# osccc.net
KiCad netlist of a schematic drawn in EAGLE
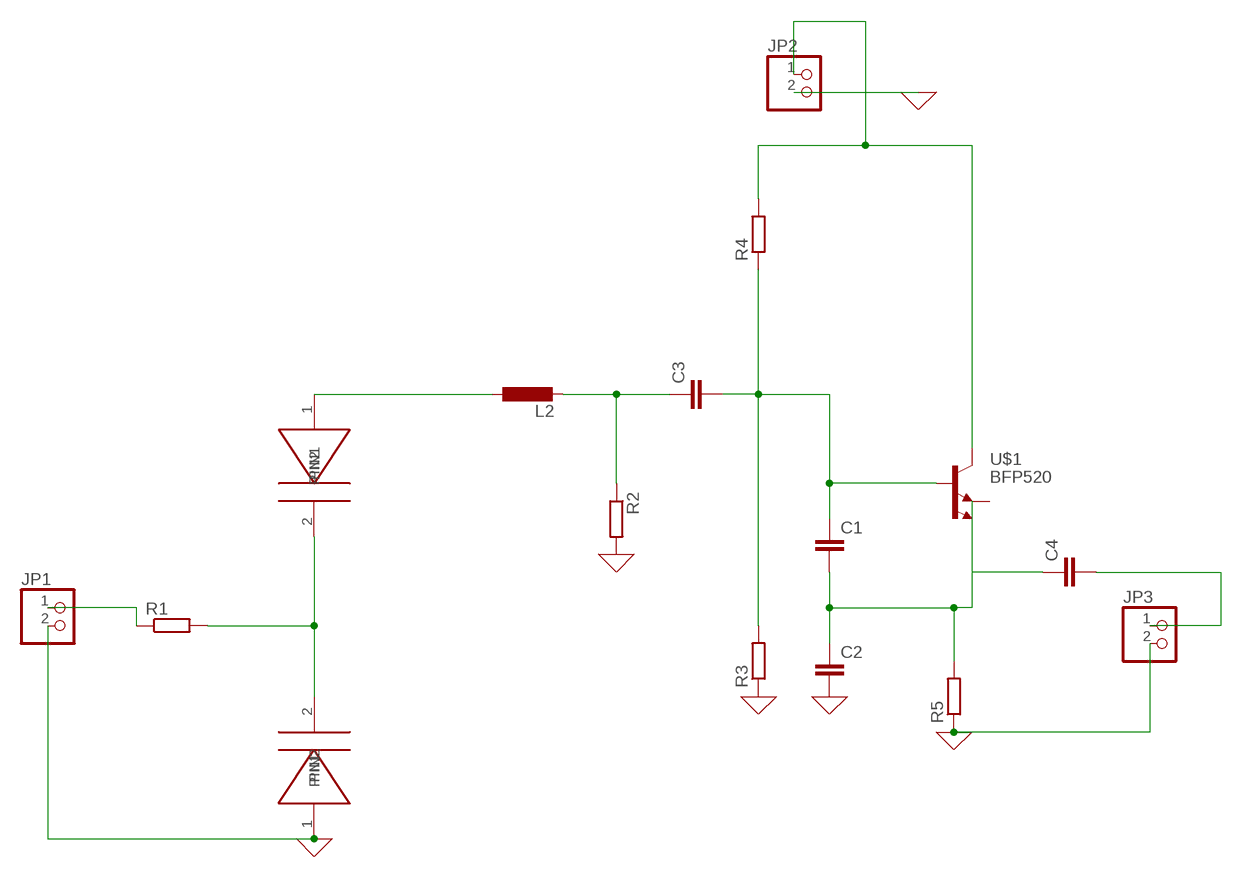
[diagram p0: schematic, sheet 1]

(export (version "E")
  (design (tool "Eeschema 10.0.6"))
  (components
    (comp (ref "C1")
      (value "C-EUC0603")
      (footprint "eagle-import:C0603")
      (libsource (lib "eagle-import") (part "C-EUC0603"))
    )
    (comp (ref "C2")
      (value "C-EUC0603")
      (footprint "eagle-import:C0603")
      (libsource (lib "eagle-import") (part "C-EUC0603"))
    )
    (comp (ref "C3")
      (value "C-EUC0603")
      (footprint "eagle-import:C0603")
      (libsource (lib "eagle-import") (part "C-EUC0603"))
    )
    (comp (ref "C4")
      (value "C-EUC0603")
      (footprint "eagle-import:C0603")
      (libsource (lib "eagle-import") (part "C-EUC0603"))
    )
    (comp (ref "JP1")
      (value "PINHD-1X2")
      (footprint "eagle-import:1X02")
      (libsource (lib "eagle-import") (part "PINHD-1X2"))
    )
    (comp (ref "JP2")
      (value "PINHD-1X2")
      (footprint "eagle-import:1X02")
      (libsource (lib "eagle-import") (part "PINHD-1X2"))
    )
    (comp (ref "JP3")
      (value "PINHD-1X2")
      (footprint "eagle-import:1X02")
      (libsource (lib "eagle-import") (part "PINHD-1X2"))
    )
    (comp (ref "L2")
      (value "L-EUL0603")
      (footprint "eagle-import:L0603")
      (libsource (lib "eagle-import") (part "L-EUL0603"))
    )
    (comp (ref "R1")
      (value "R-EU_R0603")
      (footprint "eagle-import:R0603")
      (libsource (lib "eagle-import") (part "R-EU_R0603"))
    )
    (comp (ref "R2")
      (value "R-EU_R0603")
      (footprint "eagle-import:R0603")
      (libsource (lib "eagle-import") (part "R-EU_R0603"))
    )
    (comp (ref "R3")
      (value "R-EU_R0603")
      (footprint "eagle-import:R0603")
      (libsource (lib "eagle-import") (part "R-EU_R0603"))
    )
    (comp (ref "R4")
      (value "R-EU_R0603")
      (footprint "eagle-import:R0603")
      (libsource (lib "eagle-import") (part "R-EU_R0603"))
    )
    (comp (ref "R5")
      (value "R-EU_R0603")
      (footprint "eagle-import:R0603")
      (libsource (lib "eagle-import") (part "R-EU_R0603"))
    )
    (comp (ref "U$1")
      (value "BFP520")
      (footprint "eagle-import:SOT343")
      (fields (field (name "MF") "Infineon Technologies"))
      (libsource (lib "eagle-import") (part "BFP520"))
    )
    (comp (ref "U$2")
      (value "BBY5702")
      (footprint "eagle-import:BBY5702")
      (libsource (lib "eagle-import") (part "BBY5702"))
    )
    (comp (ref "U$3")
      (value "BBY5702")
      (footprint "eagle-import:BBY5702")
      (libsource (lib "eagle-import") (part "BBY5702"))
    )
  )
  (nets
    (net (code "1") (name "GND") (class "Default")
      (node (ref "C2") (pin "2") (pinfunction "2_2") (pintype "passive"))
      (node (ref "JP1") (pin "2") (pinfunction "2_2") (pintype "passive"))
      (node (ref "JP2") (pin "2") (pinfunction "2_2") (pintype "passive"))
      (node (ref "JP3") (pin "2") (pinfunction "2_2") (pintype "passive"))
      (node (ref "R2") (pin "2") (pinfunction "2_2") (pintype "passive"))
      (node (ref "R3") (pin "1") (pinfunction "1_1") (pintype "passive"))
      (node (ref "R5") (pin "1") (pinfunction "1_1") (pintype "passive"))
      (node (ref "U$2") (pin "1") (pinfunction "PIN1_1") (pintype "bidirectional"))
    )
    (net (code "2") (name "Net-(C3-Pad1)") (class "Default")
      (node (ref "C3") (pin "1") (pinfunction "1_1") (pintype "passive"))
      (node (ref "L2") (pin "2") (pinfunction "2_2") (pintype "passive"))
      (node (ref "R2") (pin "1") (pinfunction "1_1") (pintype "passive"))
    )
    (net (code "3") (name "Net-(C4-Pad2)") (class "Default")
      (node (ref "C4") (pin "2") (pinfunction "2_2") (pintype "passive"))
      (node (ref "JP3") (pin "1") (pinfunction "1_1") (pintype "passive"))
    )
    (net (code "4") (name "Net-(JP1-Pad1)") (class "Default")
      (node (ref "JP1") (pin "1") (pinfunction "1_1") (pintype "passive"))
      (node (ref "R1") (pin "1") (pinfunction "1_1") (pintype "passive"))
    )
    (net (code "5") (name "Net-(U$1-B)") (class "Default")
      (node (ref "C1") (pin "1") (pinfunction "1_1") (pintype "passive"))
      (node (ref "C3") (pin "2") (pinfunction "2_2") (pintype "passive"))
      (node (ref "R3") (pin "2") (pinfunction "2_2") (pintype "passive"))
      (node (ref "R4") (pin "1") (pinfunction "1_1") (pintype "passive"))
      (node (ref "U$1") (pin "1") (pinfunction "B_1") (pintype "passive"))
    )
    (net (code "6") (name "Net-(U$1-C)") (class "Default")
      (node (ref "JP2") (pin "1") (pinfunction "1_1") (pintype "passive"))
      (node (ref "R4") (pin "2") (pinfunction "2_2") (pintype "passive"))
      (node (ref "U$1") (pin "3") (pinfunction "C_3") (pintype "passive"))
    )
    (net (code "7") (name "Net-(U$1-E1)") (class "Default")
      (node (ref "C1") (pin "2") (pinfunction "2_2") (pintype "passive"))
      (node (ref "C2") (pin "1") (pinfunction "1_1") (pintype "passive"))
      (node (ref "C4") (pin "1") (pinfunction "1_1") (pintype "passive"))
      (node (ref "R5") (pin "2") (pinfunction "2_2") (pintype "passive"))
      (node (ref "U$1") (pin "2") (pinfunction "E1_2") (pintype "passive"))
      (node (ref "U$1") (pin "4") (pinfunction "E2_4") (pintype "passive"))
    )
    (net (code "8") (name "Net-(U$2-PIN2)") (class "Default")
      (node (ref "R1") (pin "2") (pinfunction "2_2") (pintype "passive"))
      (node (ref "U$2") (pin "2") (pinfunction "PIN2_2") (pintype "bidirectional"))
      (node (ref "U$3") (pin "2") (pinfunction "PIN2_2") (pintype "bidirectional"))
    )
    (net (code "9") (name "Net-(U$3-PIN1)") (class "Default")
      (node (ref "L2") (pin "1") (pinfunction "1_1") (pintype "passive"))
      (node (ref "U$3") (pin "1") (pinfunction "PIN1_1") (pintype "bidirectional"))
    )
  )
)
